# input-selector.net
KiCad netlist of a schematic drawn in EAGLE
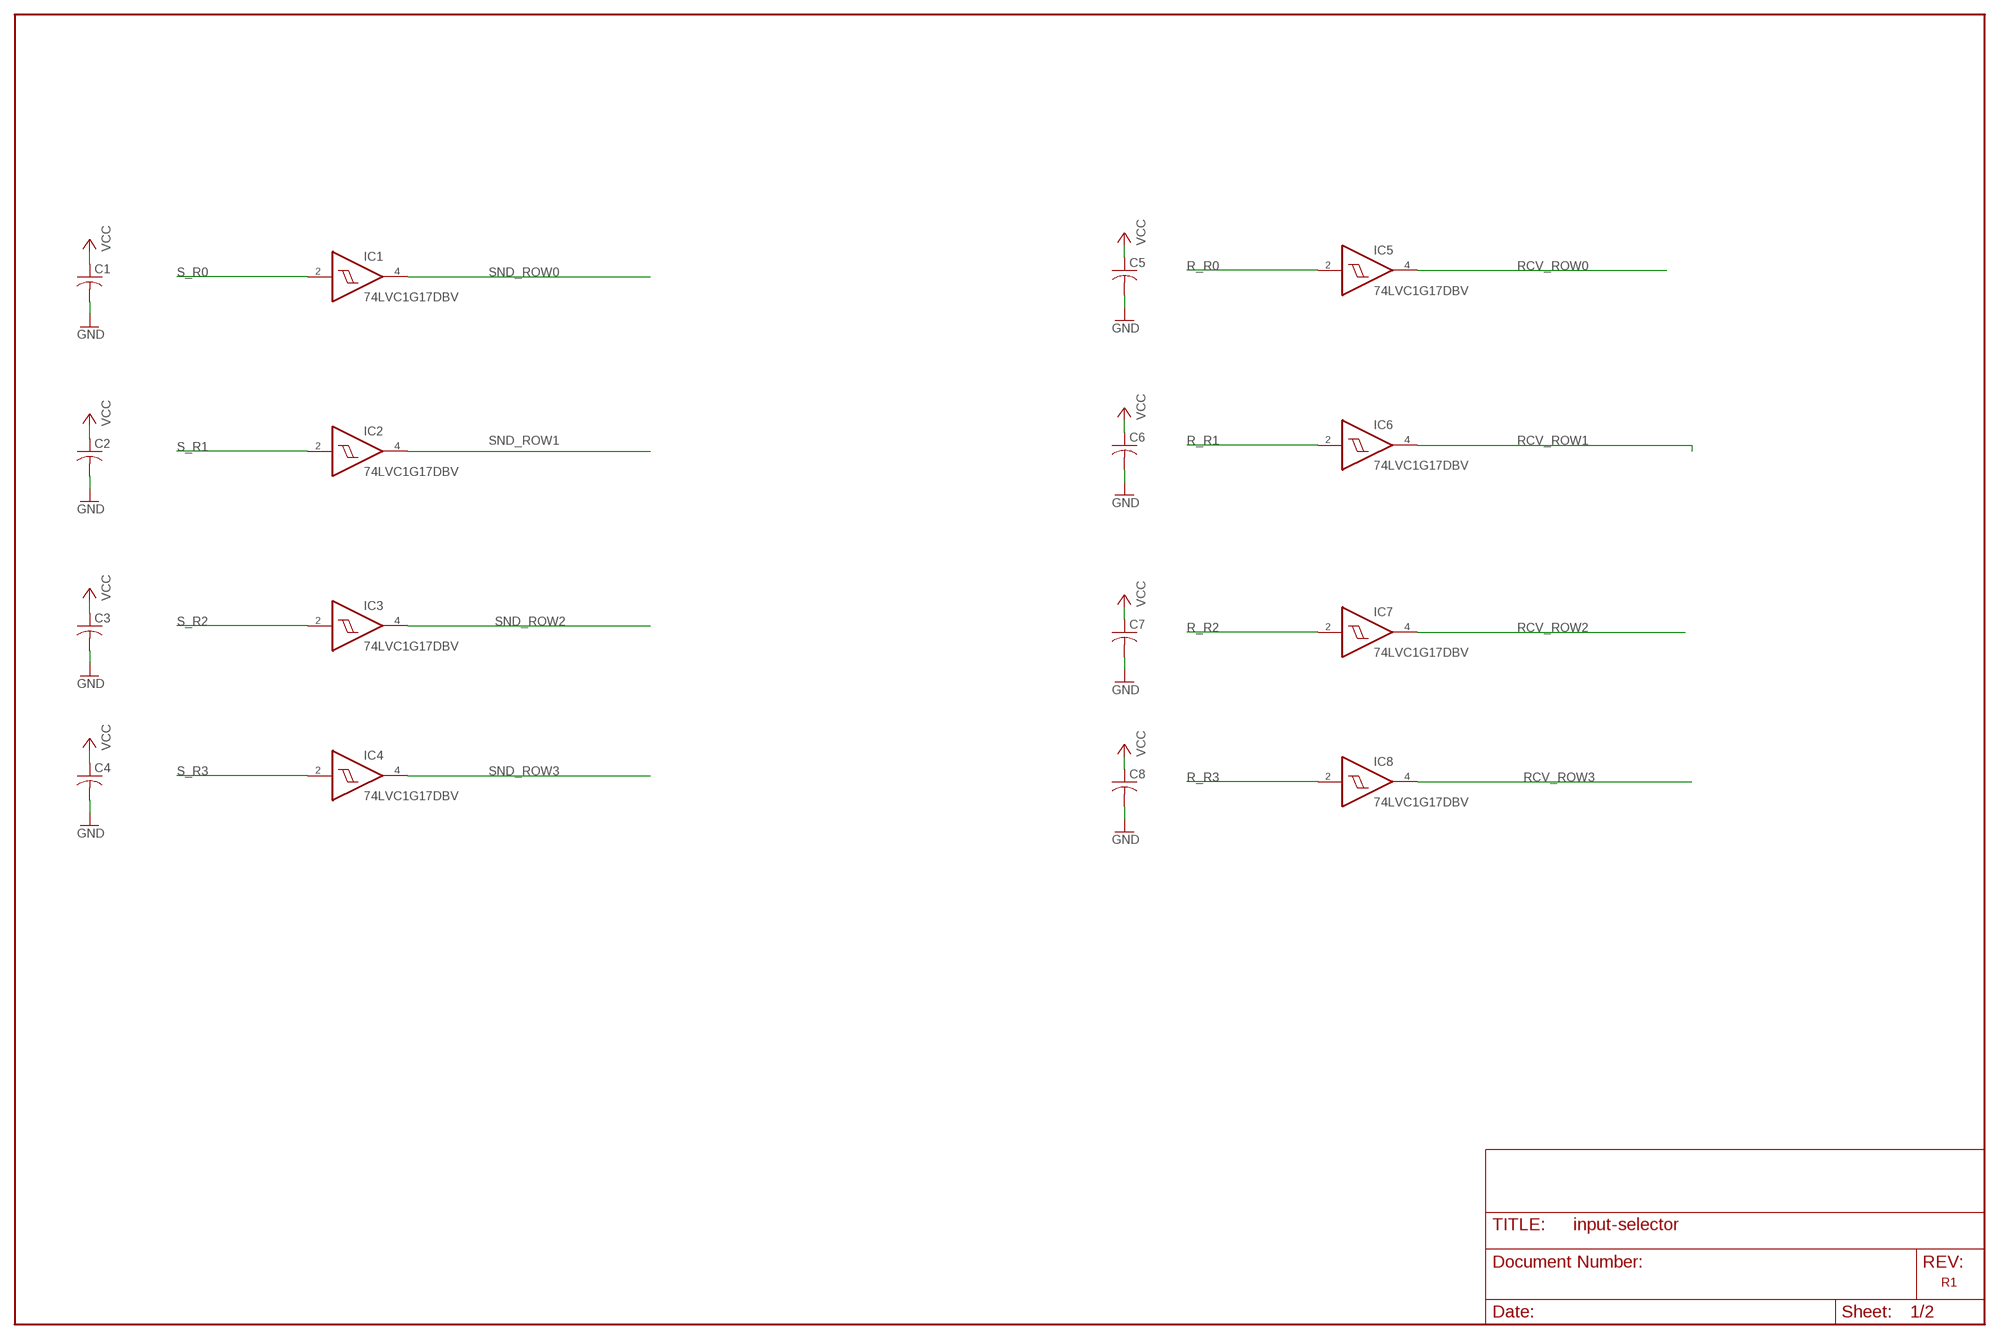
[diagram p0: schematic, sheet 1]
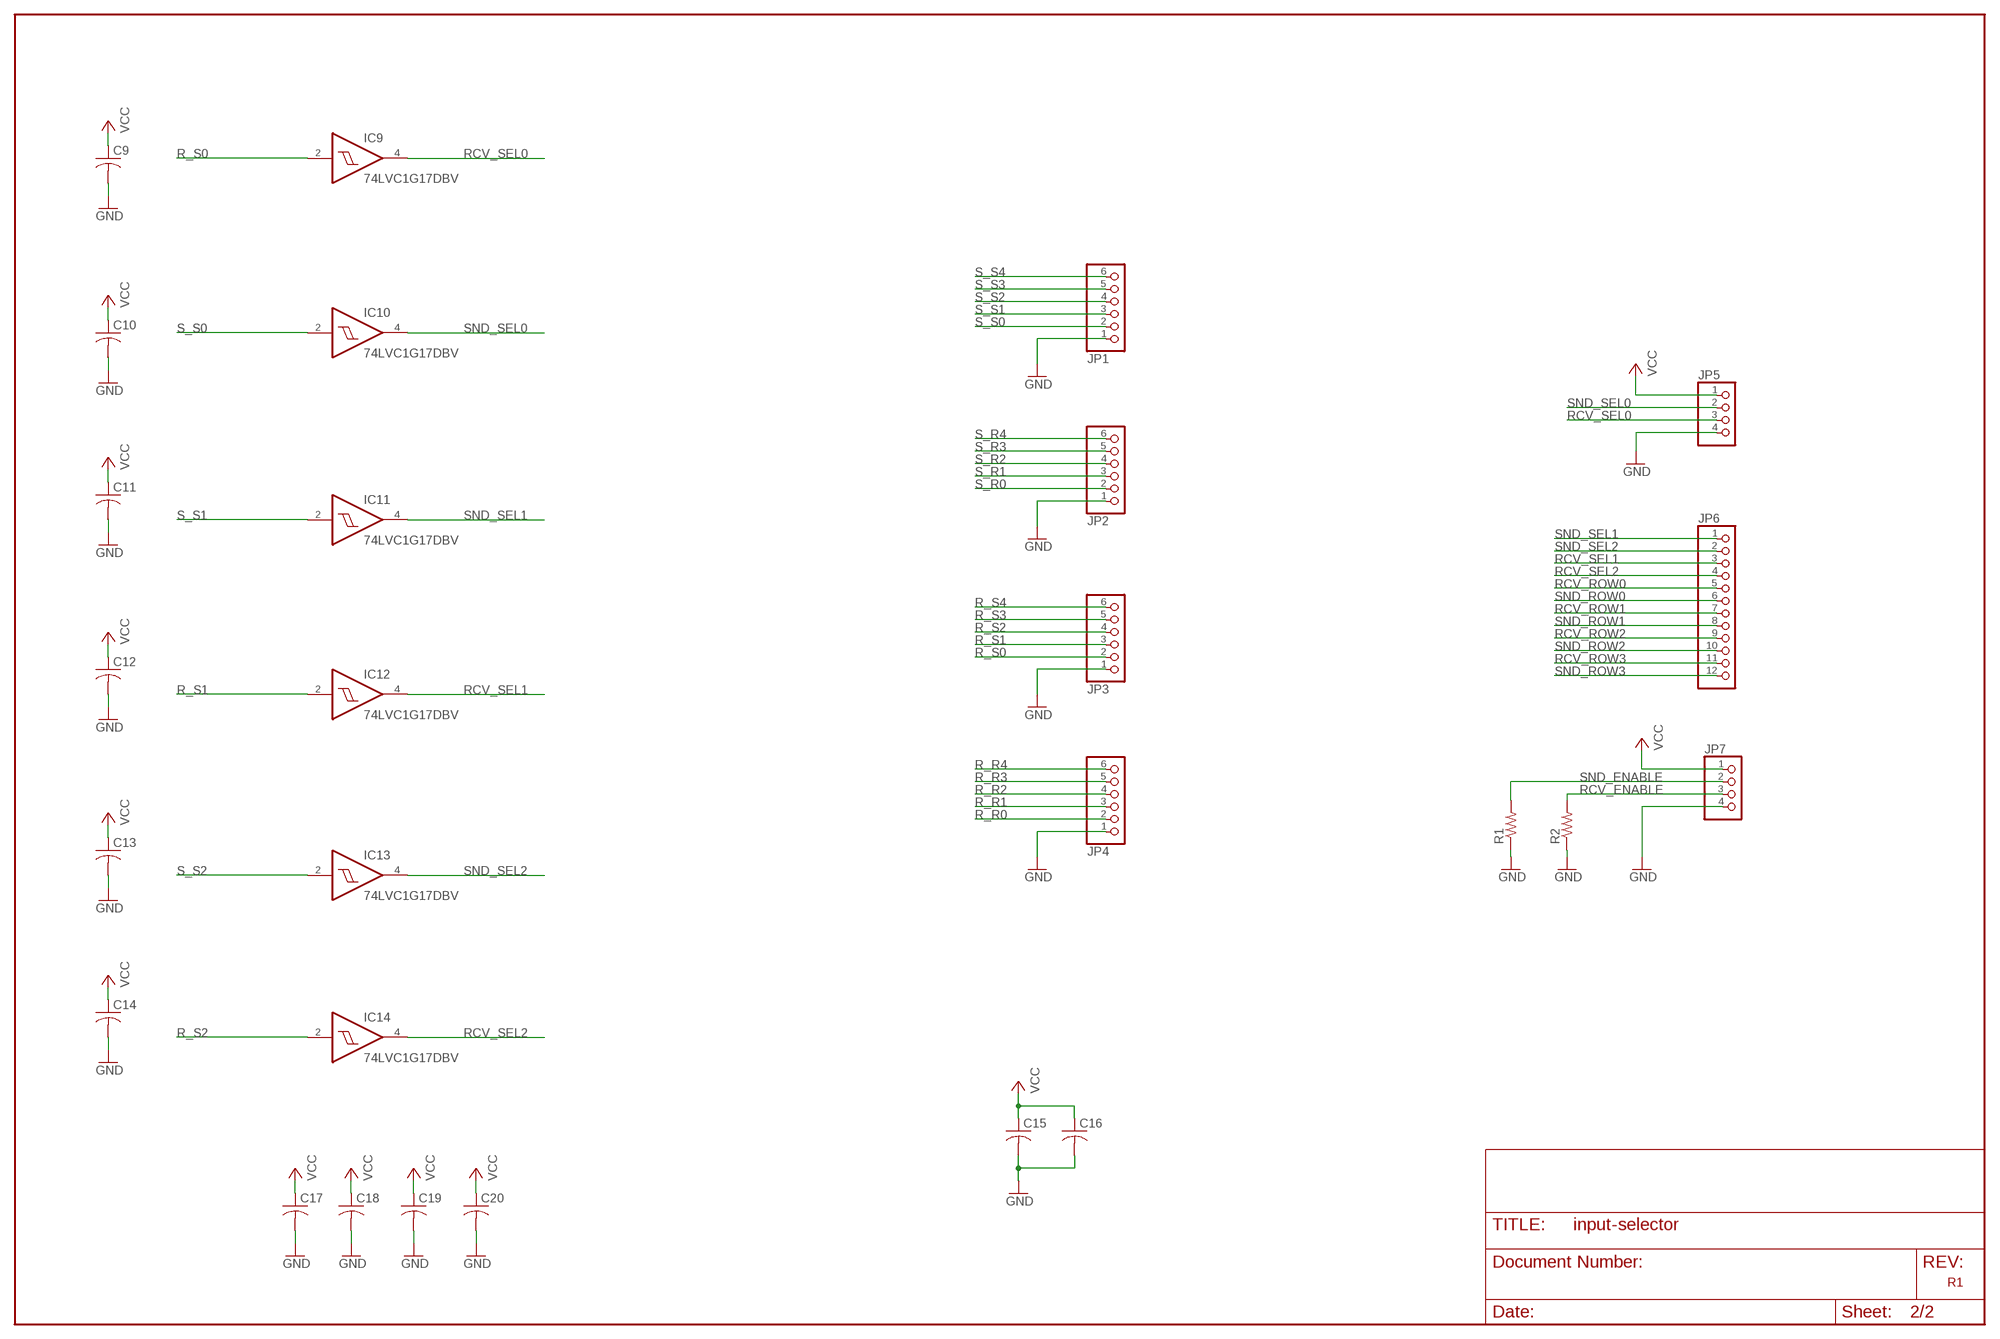
[diagram p1: schematic, sheet 2]

(export (version "E")
  (design (tool "Eeschema 10.0.6"))
  (components
    (comp (ref "C9")
      (value "C-USC0603")
      (footprint "eagle-import:C0603")
      (libsource (lib "eagle-import") (part "C-USC0603"))
    )
    (comp (ref "C10")
      (value "C-USC0603")
      (footprint "eagle-import:C0603")
      (libsource (lib "eagle-import") (part "C-USC0603"))
    )
    (comp (ref "C11")
      (value "C-USC0603")
      (footprint "eagle-import:C0603")
      (libsource (lib "eagle-import") (part "C-USC0603"))
    )
    (comp (ref "C12")
      (value "C-USC0603")
      (footprint "eagle-import:C0603")
      (libsource (lib "eagle-import") (part "C-USC0603"))
    )
    (comp (ref "C13")
      (value "C-USC0603")
      (footprint "eagle-import:C0603")
      (libsource (lib "eagle-import") (part "C-USC0603"))
    )
    (comp (ref "C14")
      (value "C-USC0603")
      (footprint "eagle-import:C0603")
      (libsource (lib "eagle-import") (part "C-USC0603"))
    )
    (comp (ref "C15")
      (value "C-USC0805")
      (footprint "eagle-import:C0805")
      (libsource (lib "eagle-import") (part "C-USC0805"))
    )
    (comp (ref "C16")
      (value "C-USC0805")
      (footprint "eagle-import:C0805")
      (libsource (lib "eagle-import") (part "C-USC0805"))
    )
    (comp (ref "C17")
      (value "C-USC0603")
      (footprint "eagle-import:C0603")
      (libsource (lib "eagle-import") (part "C-USC0603"))
    )
    (comp (ref "C18")
      (value "C-USC0603")
      (footprint "eagle-import:C0603")
      (libsource (lib "eagle-import") (part "C-USC0603"))
    )
    (comp (ref "C19")
      (value "C-USC0603")
      (footprint "eagle-import:C0603")
      (libsource (lib "eagle-import") (part "C-USC0603"))
    )
    (comp (ref "C20")
      (value "C-USC0603")
      (footprint "eagle-import:C0603")
      (libsource (lib "eagle-import") (part "C-USC0603"))
    )
    (comp (ref "IC9")
      (value "74LVC1G17DBV")
      (footprint "eagle-import:SOT23-5")
      (libsource (lib "eagle-import") (part "741G17DBVLVC"))
    )
    (comp (ref "IC10")
      (value "74LVC1G17DBV")
      (footprint "eagle-import:SOT23-5")
      (libsource (lib "eagle-import") (part "741G17DBVLVC"))
    )
    (comp (ref "IC11")
      (value "74LVC1G17DBV")
      (footprint "eagle-import:SOT23-5")
      (libsource (lib "eagle-import") (part "741G17DBVLVC"))
    )
    (comp (ref "IC12")
      (value "74LVC1G17DBV")
      (footprint "eagle-import:SOT23-5")
      (libsource (lib "eagle-import") (part "741G17DBVLVC"))
    )
    (comp (ref "IC13")
      (value "74LVC1G17DBV")
      (footprint "eagle-import:SOT23-5")
      (libsource (lib "eagle-import") (part "741G17DBVLVC"))
    )
    (comp (ref "IC14")
      (value "74LVC1G17DBV")
      (footprint "eagle-import:SOT23-5")
      (libsource (lib "eagle-import") (part "741G17DBVLVC"))
    )
    (comp (ref "JP1")
      (value "PINHD-1X6")
      (footprint "eagle-import:1X06")
      (libsource (lib "eagle-import") (part "PINHD-1X6"))
    )
    (comp (ref "JP2")
      (value "PINHD-1X6")
      (footprint "eagle-import:1X06")
      (libsource (lib "eagle-import") (part "PINHD-1X6"))
    )
    (comp (ref "JP3")
      (value "PINHD-1X6")
      (footprint "eagle-import:1X06")
      (libsource (lib "eagle-import") (part "PINHD-1X6"))
    )
    (comp (ref "JP4")
      (value "PINHD-1X6")
      (footprint "eagle-import:1X06")
      (libsource (lib "eagle-import") (part "PINHD-1X6"))
    )
    (comp (ref "JP5")
      (value "PINHD-1X4")
      (footprint "eagle-import:1X04")
      (libsource (lib "eagle-import") (part "PINHD-1X4"))
    )
    (comp (ref "JP6")
      (value "PINHD-1X12")
      (footprint "eagle-import:1X12")
      (libsource (lib "eagle-import") (part "PINHD-1X12"))
    )
    (comp (ref "JP7")
      (value "PINHD-1X4")
      (footprint "eagle-import:1X04")
      (libsource (lib "eagle-import") (part "PINHD-1X4"))
    )
    (comp (ref "R1")
      (value "R-US_R0805")
      (footprint "eagle-import:R0805")
      (libsource (lib "eagle-import") (part "R-US_R0805"))
    )
    (comp (ref "R2")
      (value "R-US_R0805")
      (footprint "eagle-import:R0805")
      (libsource (lib "eagle-import") (part "R-US_R0805"))
    )
    (comp (ref "C1")
      (value "C-USC0603")
      (footprint "eagle-import:C0603")
      (libsource (lib "eagle-import") (part "C-USC0603"))
    )
    (comp (ref "C2")
      (value "C-USC0603")
      (footprint "eagle-import:C0603")
      (libsource (lib "eagle-import") (part "C-USC0603"))
    )
    (comp (ref "C3")
      (value "C-USC0603")
      (footprint "eagle-import:C0603")
      (libsource (lib "eagle-import") (part "C-USC0603"))
    )
    (comp (ref "C4")
      (value "C-USC0603")
      (footprint "eagle-import:C0603")
      (libsource (lib "eagle-import") (part "C-USC0603"))
    )
    (comp (ref "C5")
      (value "C-USC0603")
      (footprint "eagle-import:C0603")
      (libsource (lib "eagle-import") (part "C-USC0603"))
    )
    (comp (ref "C6")
      (value "C-USC0603")
      (footprint "eagle-import:C0603")
      (libsource (lib "eagle-import") (part "C-USC0603"))
    )
    (comp (ref "C7")
      (value "C-USC0603")
      (footprint "eagle-import:C0603")
      (libsource (lib "eagle-import") (part "C-USC0603"))
    )
    (comp (ref "C8")
      (value "C-USC0603")
      (footprint "eagle-import:C0603")
      (libsource (lib "eagle-import") (part "C-USC0603"))
    )
    (comp (ref "IC1")
      (value "74LVC1G17DBV")
      (footprint "eagle-import:SOT23-5")
      (libsource (lib "eagle-import") (part "741G17DBVLVC"))
    )
    (comp (ref "IC2")
      (value "74LVC1G17DBV")
      (footprint "eagle-import:SOT23-5")
      (libsource (lib "eagle-import") (part "741G17DBVLVC"))
    )
    (comp (ref "IC3")
      (value "74LVC1G17DBV")
      (footprint "eagle-import:SOT23-5")
      (libsource (lib "eagle-import") (part "741G17DBVLVC"))
    )
    (comp (ref "IC4")
      (value "74LVC1G17DBV")
      (footprint "eagle-import:SOT23-5")
      (libsource (lib "eagle-import") (part "741G17DBVLVC"))
    )
    (comp (ref "IC5")
      (value "74LVC1G17DBV")
      (footprint "eagle-import:SOT23-5")
      (libsource (lib "eagle-import") (part "741G17DBVLVC"))
    )
    (comp (ref "IC6")
      (value "74LVC1G17DBV")
      (footprint "eagle-import:SOT23-5")
      (libsource (lib "eagle-import") (part "741G17DBVLVC"))
    )
    (comp (ref "IC7")
      (value "74LVC1G17DBV")
      (footprint "eagle-import:SOT23-5")
      (libsource (lib "eagle-import") (part "741G17DBVLVC"))
    )
    (comp (ref "IC8")
      (value "74LVC1G17DBV")
      (footprint "eagle-import:SOT23-5")
      (libsource (lib "eagle-import") (part "741G17DBVLVC"))
    )
  )
  (nets
    (net (code "1") (name "GND") (class "Default")
      (node (ref "C1") (pin "2") (pinfunction "2_2") (pintype "passive"))
      (node (ref "C10") (pin "2") (pinfunction "2_2") (pintype "passive"))
      (node (ref "C11") (pin "2") (pinfunction "2_2") (pintype "passive"))
      (node (ref "C12") (pin "2") (pinfunction "2_2") (pintype "passive"))
      (node (ref "C13") (pin "2") (pinfunction "2_2") (pintype "passive"))
      (node (ref "C14") (pin "2") (pinfunction "2_2") (pintype "passive"))
      (node (ref "C15") (pin "2") (pinfunction "2_2") (pintype "passive"))
      (node (ref "C16") (pin "2") (pinfunction "2_2") (pintype "passive"))
      (node (ref "C17") (pin "2") (pinfunction "2_2") (pintype "passive"))
      (node (ref "C18") (pin "2") (pinfunction "2_2") (pintype "passive"))
      (node (ref "C19") (pin "2") (pinfunction "2_2") (pintype "passive"))
      (node (ref "C2") (pin "2") (pinfunction "2_2") (pintype "passive"))
      (node (ref "C20") (pin "2") (pinfunction "2_2") (pintype "passive"))
      (node (ref "C3") (pin "2") (pinfunction "2_2") (pintype "passive"))
      (node (ref "C4") (pin "2") (pinfunction "2_2") (pintype "passive"))
      (node (ref "C5") (pin "2") (pinfunction "2_2") (pintype "passive"))
      (node (ref "C6") (pin "2") (pinfunction "2_2") (pintype "passive"))
      (node (ref "C7") (pin "2") (pinfunction "2_2") (pintype "passive"))
      (node (ref "C8") (pin "2") (pinfunction "2_2") (pintype "passive"))
      (node (ref "C9") (pin "2") (pinfunction "2_2") (pintype "passive"))
      (node (ref "JP1") (pin "1") (pinfunction "1_1") (pintype "passive"))
      (node (ref "JP2") (pin "1") (pinfunction "1_1") (pintype "passive"))
      (node (ref "JP3") (pin "1") (pinfunction "1_1") (pintype "passive"))
      (node (ref "JP4") (pin "1") (pinfunction "1_1") (pintype "passive"))
      (node (ref "JP5") (pin "4") (pinfunction "4_4") (pintype "passive"))
      (node (ref "JP7") (pin "4") (pinfunction "4_4") (pintype "passive"))
      (node (ref "R1") (pin "1") (pinfunction "1_1") (pintype "passive"))
      (node (ref "R2") (pin "1") (pinfunction "1_1") (pintype "passive"))
    )
    (net (code "2") (name "RCV_ENABLE") (class "Default")
      (node (ref "JP7") (pin "3") (pinfunction "3_3") (pintype "passive"))
      (node (ref "R2") (pin "2") (pinfunction "2_2") (pintype "passive"))
    )
    (net (code "3") (name "RCV_ROW0") (class "Default")
      (node (ref "IC5") (pin "4") (pinfunction "O_4") (pintype "output"))
      (node (ref "JP6") (pin "5") (pinfunction "5_5") (pintype "passive"))
    )
    (net (code "4") (name "RCV_ROW1") (class "Default")
      (node (ref "IC6") (pin "4") (pinfunction "O_4") (pintype "output"))
      (node (ref "JP6") (pin "7") (pinfunction "7_7") (pintype "passive"))
    )
    (net (code "5") (name "RCV_ROW2") (class "Default")
      (node (ref "IC7") (pin "4") (pinfunction "O_4") (pintype "output"))
      (node (ref "JP6") (pin "9") (pinfunction "9_9") (pintype "passive"))
    )
    (net (code "6") (name "RCV_ROW3") (class "Default")
      (node (ref "IC8") (pin "4") (pinfunction "O_4") (pintype "output"))
      (node (ref "JP6") (pin "11") (pinfunction "11_11") (pintype "passive"))
    )
    (net (code "7") (name "RCV_SEL0") (class "Default")
      (node (ref "IC9") (pin "4") (pinfunction "O_4") (pintype "output"))
      (node (ref "JP5") (pin "3") (pinfunction "3_3") (pintype "passive"))
    )
    (net (code "8") (name "RCV_SEL1") (class "Default")
      (node (ref "IC12") (pin "4") (pinfunction "O_4") (pintype "output"))
      (node (ref "JP6") (pin "3") (pinfunction "3_3") (pintype "passive"))
    )
    (net (code "9") (name "RCV_SEL2") (class "Default")
      (node (ref "IC14") (pin "4") (pinfunction "O_4") (pintype "output"))
      (node (ref "JP6") (pin "4") (pinfunction "4_4") (pintype "passive"))
    )
    (net (code "10") (name "R_R0") (class "Default")
      (node (ref "IC5") (pin "2") (pinfunction "I_2") (pintype "input"))
      (node (ref "JP4") (pin "2") (pinfunction "2_2") (pintype "passive"))
    )
    (net (code "11") (name "R_R1") (class "Default")
      (node (ref "IC6") (pin "2") (pinfunction "I_2") (pintype "input"))
      (node (ref "JP4") (pin "3") (pinfunction "3_3") (pintype "passive"))
    )
    (net (code "12") (name "R_R2") (class "Default")
      (node (ref "IC7") (pin "2") (pinfunction "I_2") (pintype "input"))
      (node (ref "JP4") (pin "4") (pinfunction "4_4") (pintype "passive"))
    )
    (net (code "13") (name "R_R3") (class "Default")
      (node (ref "IC8") (pin "2") (pinfunction "I_2") (pintype "input"))
      (node (ref "JP4") (pin "5") (pinfunction "5_5") (pintype "passive"))
    )
    (net (code "14") (name "R_R4") (class "Default")
      (node (ref "JP4") (pin "6") (pinfunction "6_6") (pintype "passive"))
    )
    (net (code "15") (name "R_S0") (class "Default")
      (node (ref "IC9") (pin "2") (pinfunction "I_2") (pintype "input"))
      (node (ref "JP3") (pin "2") (pinfunction "2_2") (pintype "passive"))
    )
    (net (code "16") (name "R_S1") (class "Default")
      (node (ref "IC12") (pin "2") (pinfunction "I_2") (pintype "input"))
      (node (ref "JP3") (pin "3") (pinfunction "3_3") (pintype "passive"))
    )
    (net (code "17") (name "R_S2") (class "Default")
      (node (ref "IC14") (pin "2") (pinfunction "I_2") (pintype "input"))
      (node (ref "JP3") (pin "4") (pinfunction "4_4") (pintype "passive"))
    )
    (net (code "18") (name "R_S3") (class "Default")
      (node (ref "JP3") (pin "5") (pinfunction "5_5") (pintype "passive"))
    )
    (net (code "19") (name "R_S4") (class "Default")
      (node (ref "JP3") (pin "6") (pinfunction "6_6") (pintype "passive"))
    )
    (net (code "20") (name "SND_ENABLE") (class "Default")
      (node (ref "JP7") (pin "2") (pinfunction "2_2") (pintype "passive"))
      (node (ref "R1") (pin "2") (pinfunction "2_2") (pintype "passive"))
    )
    (net (code "21") (name "SND_ROW0") (class "Default")
      (node (ref "IC1") (pin "4") (pinfunction "O_4") (pintype "output"))
      (node (ref "JP6") (pin "6") (pinfunction "6_6") (pintype "passive"))
    )
    (net (code "22") (name "SND_ROW1") (class "Default")
      (node (ref "IC2") (pin "4") (pinfunction "O_4") (pintype "output"))
      (node (ref "JP6") (pin "8") (pinfunction "8_8") (pintype "passive"))
    )
    (net (code "23") (name "SND_ROW2") (class "Default")
      (node (ref "IC3") (pin "4") (pinfunction "O_4") (pintype "output"))
      (node (ref "JP6") (pin "10") (pinfunction "10_10") (pintype "passive"))
    )
    (net (code "24") (name "SND_ROW3") (class "Default")
      (node (ref "IC4") (pin "4") (pinfunction "O_4") (pintype "output"))
      (node (ref "JP6") (pin "12") (pinfunction "12_12") (pintype "passive"))
    )
    (net (code "25") (name "SND_SEL0") (class "Default")
      (node (ref "IC10") (pin "4") (pinfunction "O_4") (pintype "output"))
      (node (ref "JP5") (pin "2") (pinfunction "2_2") (pintype "passive"))
    )
    (net (code "26") (name "SND_SEL1") (class "Default")
      (node (ref "IC11") (pin "4") (pinfunction "O_4") (pintype "output"))
      (node (ref "JP6") (pin "1") (pinfunction "1_1") (pintype "passive"))
    )
    (net (code "27") (name "SND_SEL2") (class "Default")
      (node (ref "IC13") (pin "4") (pinfunction "O_4") (pintype "output"))
      (node (ref "JP6") (pin "2") (pinfunction "2_2") (pintype "passive"))
    )
    (net (code "28") (name "S_R0") (class "Default")
      (node (ref "IC1") (pin "2") (pinfunction "I_2") (pintype "input"))
      (node (ref "JP2") (pin "2") (pinfunction "2_2") (pintype "passive"))
    )
    (net (code "29") (name "S_R1") (class "Default")
      (node (ref "IC2") (pin "2") (pinfunction "I_2") (pintype "input"))
      (node (ref "JP2") (pin "3") (pinfunction "3_3") (pintype "passive"))
    )
    (net (code "30") (name "S_R2") (class "Default")
      (node (ref "IC3") (pin "2") (pinfunction "I_2") (pintype "input"))
      (node (ref "JP2") (pin "4") (pinfunction "4_4") (pintype "passive"))
    )
    (net (code "31") (name "S_R3") (class "Default")
      (node (ref "IC4") (pin "2") (pinfunction "I_2") (pintype "input"))
      (node (ref "JP2") (pin "5") (pinfunction "5_5") (pintype "passive"))
    )
    (net (code "32") (name "S_R4") (class "Default")
      (node (ref "JP2") (pin "6") (pinfunction "6_6") (pintype "passive"))
    )
    (net (code "33") (name "S_S0") (class "Default")
      (node (ref "IC10") (pin "2") (pinfunction "I_2") (pintype "input"))
      (node (ref "JP1") (pin "2") (pinfunction "2_2") (pintype "passive"))
    )
    (net (code "34") (name "S_S1") (class "Default")
      (node (ref "IC11") (pin "2") (pinfunction "I_2") (pintype "input"))
      (node (ref "JP1") (pin "3") (pinfunction "3_3") (pintype "passive"))
    )
    (net (code "35") (name "S_S2") (class "Default")
      (node (ref "IC13") (pin "2") (pinfunction "I_2") (pintype "input"))
      (node (ref "JP1") (pin "4") (pinfunction "4_4") (pintype "passive"))
    )
    (net (code "36") (name "S_S3") (class "Default")
      (node (ref "JP1") (pin "5") (pinfunction "5_5") (pintype "passive"))
    )
    (net (code "37") (name "S_S4") (class "Default")
      (node (ref "JP1") (pin "6") (pinfunction "6_6") (pintype "passive"))
    )
    (net (code "38") (name "VCC") (class "Default")
      (node (ref "C1") (pin "1") (pinfunction "1_1") (pintype "passive"))
      (node (ref "C10") (pin "1") (pinfunction "1_1") (pintype "passive"))
      (node (ref "C11") (pin "1") (pinfunction "1_1") (pintype "passive"))
      (node (ref "C12") (pin "1") (pinfunction "1_1") (pintype "passive"))
      (node (ref "C13") (pin "1") (pinfunction "1_1") (pintype "passive"))
      (node (ref "C14") (pin "1") (pinfunction "1_1") (pintype "passive"))
      (node (ref "C15") (pin "1") (pinfunction "1_1") (pintype "passive"))
      (node (ref "C16") (pin "1") (pinfunction "1_1") (pintype "passive"))
      (node (ref "C17") (pin "1") (pinfunction "1_1") (pintype "passive"))
      (node (ref "C18") (pin "1") (pinfunction "1_1") (pintype "passive"))
      (node (ref "C19") (pin "1") (pinfunction "1_1") (pintype "passive"))
      (node (ref "C2") (pin "1") (pinfunction "1_1") (pintype "passive"))
      (node (ref "C20") (pin "1") (pinfunction "1_1") (pintype "passive"))
      (node (ref "C3") (pin "1") (pinfunction "1_1") (pintype "passive"))
      (node (ref "C4") (pin "1") (pinfunction "1_1") (pintype "passive"))
      (node (ref "C5") (pin "1") (pinfunction "1_1") (pintype "passive"))
      (node (ref "C6") (pin "1") (pinfunction "1_1") (pintype "passive"))
      (node (ref "C7") (pin "1") (pinfunction "1_1") (pintype "passive"))
      (node (ref "C8") (pin "1") (pinfunction "1_1") (pintype "passive"))
      (node (ref "C9") (pin "1") (pinfunction "1_1") (pintype "passive"))
      (node (ref "JP5") (pin "1") (pinfunction "1_1") (pintype "passive"))
      (node (ref "JP7") (pin "1") (pinfunction "1_1") (pintype "passive"))
    )
  )
)
